# Power.net
KiCad netlist of a schematic drawn in Altium Designer
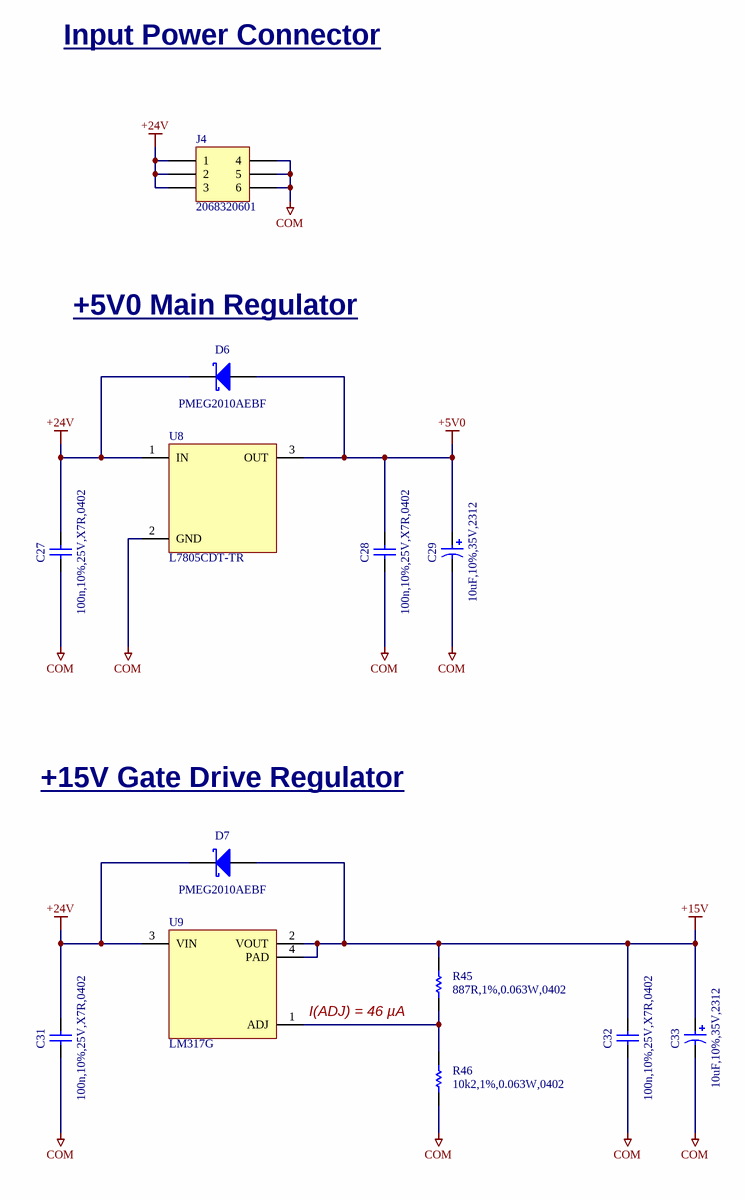
[diagram p0: Power.SchDoc]

(export (version "E")
  (design (tool "Eeschema 10.0.6"))
  (components
    (comp (ref "C27")
      (value "100n,10%,25V,X7R,0402")
      (footprint "CAPC1005X06N")
      (description "0.1ï¿½F ï¿½10% 25V Ceramic Capacitor X7R 0402 (1005 Metric)")
      (fields
        (field (name "MANUFACTURER 1 PART NUMBER") "GRM155R71E104KE14J")
        (field (name "VENDOR 1 PART NUMBER") "490-14603-1-ND")
        (field (name "CREATEDBY") "Judd Foster")
      )
      (libsource (lib "Component Library") (part "CAP,Cer,100nF,10%,25V,X7R,0402"))
    )
    (comp (ref "C28")
      (value "100n,10%,25V,X7R,0402")
      (footprint "CAPC1005X06N")
      (description "0.1ï¿½F ï¿½10% 25V Ceramic Capacitor X7R 0402 (1005 Metric)")
      (fields
        (field (name "MANUFACTURER 1 PART NUMBER") "GRM155R71E104KE14J")
        (field (name "VENDOR 1 PART NUMBER") "490-14603-1-ND")
        (field (name "CREATEDBY") "Judd Foster")
      )
      (libsource (lib "Component Library") (part "CAP,Cer,100nF,10%,25V,X7R,0402"))
    )
    (comp (ref "C29")
      (value "10uF,10%,35V,2312")
      (footprint "KYOCERA_PKG_TAJC")
      (description "10 ÂµF Molded Tantalum Capacitors 35 V 2312 (6032 Metric) 1.6Ohm")
      (fields
        (field (name "MANUFACTURER 1 PART NUMBER") "TAJC106K035RNJ")
        (field (name "VENDOR 1 PART NUMBER") "478-1701-1-ND")
        (field (name "CREATEDBY") "Judd Foster")
      )
      (libsource (lib "Component Library") (part "CAP,Tant,10uF,10%,35V,2312"))
    )
    (comp (ref "C31")
      (value "100n,10%,25V,X7R,0402")
      (footprint "CAPC1005X06N")
      (description "0.1ï¿½F ï¿½10% 25V Ceramic Capacitor X7R 0402 (1005 Metric)")
      (fields
        (field (name "MANUFACTURER 1 PART NUMBER") "GRM155R71E104KE14J")
        (field (name "VENDOR 1 PART NUMBER") "490-14603-1-ND")
        (field (name "CREATEDBY") "Judd Foster")
      )
      (libsource (lib "Component Library") (part "CAP,Cer,100nF,10%,25V,X7R,0402"))
    )
    (comp (ref "C32")
      (value "100n,10%,25V,X7R,0402")
      (footprint "CAPC1005X06N")
      (description "0.1ï¿½F ï¿½10% 25V Ceramic Capacitor X7R 0402 (1005 Metric)")
      (fields
        (field (name "MANUFACTURER 1 PART NUMBER") "GRM155R71E104KE14J")
        (field (name "VENDOR 1 PART NUMBER") "490-14603-1-ND")
        (field (name "CREATEDBY") "Judd Foster")
      )
      (libsource (lib "Component Library") (part "CAP,Cer,100nF,10%,25V,X7R,0402"))
    )
    (comp (ref "C33")
      (value "10uF,10%,35V,2312")
      (footprint "KYOCERA_PKG_TAJC")
      (description "10 ÂµF Molded Tantalum Capacitors 35 V 2312 (6032 Metric) 1.6Ohm")
      (fields
        (field (name "MANUFACTURER 1 PART NUMBER") "TAJC106K035RNJ")
        (field (name "VENDOR 1 PART NUMBER") "478-1701-1-ND")
        (field (name "CREATEDBY") "Judd Foster")
      )
      (libsource (lib "Component Library") (part "CAP,Tant,10uF,10%,35V,2312"))
    )
    (comp (ref "D6")
      (value "PMEG2010AEBF")
      (footprint "NEXPERIA_PKG_SOD523")
      (description "Diode 20 V 1A Surface Mount SOD-523")
      (fields (field (name "VENDOR 1 PART NUMBER") "1727-8539-1-ND") (field (name "CREATEDBY") "Judd Foster"))
      (libsource (lib "Component Library") (part "DIODE,Schottky,20V,1A,SOD523"))
    )
    (comp (ref "D7")
      (value "PMEG2010AEBF")
      (footprint "NEXPERIA_PKG_SOD523")
      (description "Diode 20 V 1A Surface Mount SOD-523")
      (fields (field (name "VENDOR 1 PART NUMBER") "1727-8539-1-ND") (field (name "CREATEDBY") "Judd Foster"))
      (libsource (lib "Component Library") (part "DIODE,Schottky,20V,1A,SOD523"))
    )
    (comp (ref "J4")
      (value "2068320601")
      (footprint "MOLEX_2068320601")
      (description "Connector Header Through Hole 6 position 0.118\" (3.00mm)")
      (fields (field (name "VENDOR 1 PART NUMBER") "WM26556-ND") (field (name "CREATEDBY") "Judd Foster"))
      (libsource (lib "Component Library") (part "Conn,Micro-Fit,Hdr,6Pos,Vert,Thru"))
    )
    (comp (ref "R45")
      (value "887R,1%,0.063W,0402")
      (footprint "RESC1005X04N")
      (description "887Î© 62.5mW 50V Â±200ppm/â„ƒ Â±1% Thick Film Resistors 0402 Chip Resistor - Surface Mount ROHS")
      (fields
        (field (name "MANUFACTURER 1 PART NUMBER") "RC-02W8870FT")
        (field (name "VENDOR 1 PART NUMBER") "C321640")
        (field (name "CREATEDBY") "Judd Foster")
      )
      (libsource (lib "Component Library") (part "RES,887R,1%,0.063W,0402"))
    )
    (comp (ref "R46")
      (value "10k2,1%,0.063W,0402")
      (footprint "RESC1005X04N")
      (description "10.2 kOhms Â±1% 0.063W, 1/16W Chip Resistor 0402 (1005 Metric) Moisture Resistant Thick Film")
      (fields
        (field (name "MANUFACTURER 1 PART NUMBER") "RC0402FR-0710K2L")
        (field (name "VENDOR 1 PART NUMBER") "YAG2950CT-ND")
        (field (name "CREATEDBY") "Judd Foster")
      )
      (libsource (lib "Component Library") (part "RES,10k2,1%,0.063W,0402"))
    )
    (comp (ref "U8")
      (value "L7805CDT-TR")
      (footprint "STMICRO_L7805CDT-TR")
      (fields (field (name "VENDOR 1 PART NUMBER") "C310413") (field (name "CREATEDBY") "Judd Foster"))
      (libsource (lib "Component Library") (part "L7805CDT-TR"))
    )
    (comp (ref "U9")
      (value "LM317G")
      (footprint "UMW_PKG_SOT223-3L")
      (fields (field (name "VENDOR 1 PART NUMBER") "C347367") (field (name "CREATEDBY") "Judd Foster"))
      (libsource (lib "Component Library") (part "LM317G"))
    )
  )
  (nets
    (net (code "1") (name "+5V0") (class "Default")
      (node (ref "C28") (pin "2") (pinfunction "2_2") (pintype "passive"))
      (node (ref "C29") (pin "1") (pinfunction "1_1") (pintype "passive"))
      (node (ref "D6") (pin "2") (pinfunction "A_2") (pintype "passive"))
      (node (ref "U8") (pin "3") (pinfunction "OUT_3") (pintype "passive"))
    )
    (net (code "2") (name "+15V") (class "Default")
      (node (ref "C32") (pin "2") (pinfunction "2_2") (pintype "passive"))
      (node (ref "C33") (pin "1") (pinfunction "1_1") (pintype "passive"))
      (node (ref "D7") (pin "2") (pinfunction "A_2") (pintype "passive"))
      (node (ref "R45") (pin "2") (pinfunction "2_2") (pintype "passive"))
      (node (ref "U9") (pin "2") (pinfunction "VOUT_2") (pintype "power_in"))
      (node (ref "U9") (pin "4") (pinfunction "PAD_4") (pintype "power_in"))
    )
    (net (code "3") (name "+24V") (class "Default")
      (node (ref "C27") (pin "2") (pinfunction "2_2") (pintype "passive"))
      (node (ref "C31") (pin "2") (pinfunction "2_2") (pintype "passive"))
      (node (ref "D6") (pin "1") (pinfunction "K_1") (pintype "passive"))
      (node (ref "D7") (pin "1") (pinfunction "K_1") (pintype "passive"))
      (node (ref "J4") (pin "1") (pinfunction "1_1") (pintype "passive"))
      (node (ref "J4") (pin "2") (pinfunction "2_2") (pintype "passive"))
      (node (ref "J4") (pin "3") (pinfunction "3_3") (pintype "passive"))
      (node (ref "U8") (pin "1") (pinfunction "IN_1") (pintype "passive"))
      (node (ref "U9") (pin "3") (pinfunction "VIN_3") (pintype "power_in"))
    )
    (net (code "4") (name "COM") (class "Default")
      (node (ref "C27") (pin "1") (pinfunction "1_1") (pintype "passive"))
      (node (ref "C28") (pin "1") (pinfunction "1_1") (pintype "passive"))
      (node (ref "C29") (pin "2") (pinfunction "2_2") (pintype "passive"))
      (node (ref "C31") (pin "1") (pinfunction "1_1") (pintype "passive"))
      (node (ref "C32") (pin "1") (pinfunction "1_1") (pintype "passive"))
      (node (ref "C33") (pin "2") (pinfunction "2_2") (pintype "passive"))
      (node (ref "J4") (pin "4") (pinfunction "4_4") (pintype "passive"))
      (node (ref "J4") (pin "5") (pinfunction "5_5") (pintype "passive"))
      (node (ref "J4") (pin "6") (pinfunction "6_6") (pintype "passive"))
      (node (ref "R46") (pin "1") (pinfunction "1_1") (pintype "passive"))
      (node (ref "U8") (pin "2") (pinfunction "GND_2") (pintype "passive"))
    )
    (net (code "5") (name "Net-(U9-ADJ)") (class "Default")
      (node (ref "R45") (pin "1") (pinfunction "1_1") (pintype "passive"))
      (node (ref "R46") (pin "2") (pinfunction "2_2") (pintype "passive"))
      (node (ref "U9") (pin "1") (pinfunction "ADJ_1") (pintype "power_in"))
    )
  )
)
